# 5_Com_channel.net
KiCad netlist of a schematic drawn in Altium Designer
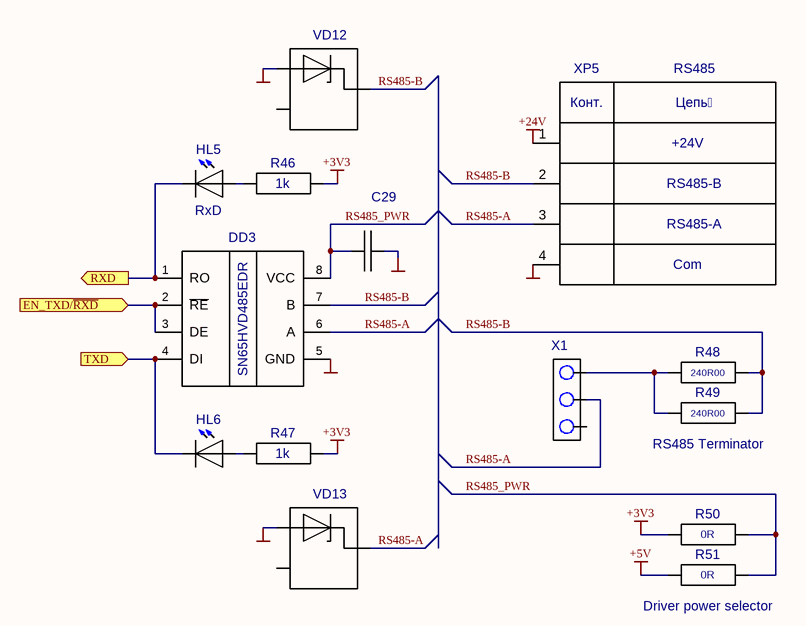
[diagram p0: 5 Com channel.SchDoc]

(export (version "E")
  (design (tool "Eeschema 10.0.6"))
  (components
    (comp (ref "C29")
      (value "C0402")
      (footprint "конденсаторы:0402_CAP")
      (libsource (lib "Com via Eth") (part "C0402"))
    )
    (comp (ref "DD3")
      (value "SN65HVD485EDR")
      (footprint "SO8")
      (description "ADM485AR")
      (libsource (lib "*") (part "ADM485AR"))
    )
    (comp (ref "HL5")
      (value "KP-2012MGC")
      (footprint "индикаторные эл-ты:KP-2012_GRN")
      (libsource (lib "*") (part "KP-2012"))
    )
    (comp (ref "HL6")
      (value "KP-2012SYC")
      (footprint "индикаторные эл-ты:KP-2012_YEL")
      (libsource (lib "*") (part "KP-2012"))
    )
    (comp (ref "R46")
      (value "1k")
      (footprint "резисторы:0603_RES")
      (description "R0603")
      (libsource (lib "*") (part "R0603"))
    )
    (comp (ref "R47")
      (value "1k")
      (footprint "резисторы:0603_RES")
      (description "R0603")
      (libsource (lib "*") (part "R0603"))
    )
    (comp (ref "R48")
      (value "240R00")
      (footprint "резисторы:0805_RES")
      (description "R0805")
      (libsource (lib "Strobe and com via fiber") (part "R0805"))
    )
    (comp (ref "R49")
      (value "240R00")
      (footprint "резисторы:0805_RES")
      (description "R0805")
      (libsource (lib "Strobe and com via fiber") (part "R0805"))
    )
    (comp (ref "R50")
      (value "0R")
      (footprint "резисторы:0402_RES")
      (description "R0402")
      (libsource (lib "резисторы") (part "R0402"))
    )
    (comp (ref "R51")
      (value "0R")
      (footprint "резисторы:0402_RES")
      (description "R0402")
      (libsource (lib "резисторы") (part "R0402"))
    )
    (comp (ref "VD12")
      (value "GSOT12-E3-08")
      (footprint "диоды:SOT-23-(2)")
      (description "Single-line ESD protection device\r\n± 30 kV contact discharge\r\n± 30 kV air discharge")
      (libsource (lib "диоды") (part "GSOT12C"))
    )
    (comp (ref "VD13")
      (value "GSOT12-E3-08")
      (footprint "диоды:SOT-23-(2)")
      (description "Single-line ESD protection device\r\n± 30 kV contact discharge\r\n± 30 kV air discharge")
      (libsource (lib "диоды") (part "GSOT12C"))
    )
    (comp (ref "X1")
      (value "DS1025-01-1*3 P8BV1")
      (footprint "PLS2-3")
      (description "PLS2-3")
      (libsource (lib "*") (part "PLS2-3"))
    )
    (comp (ref "XP5") (value "PH-4") (footprint "PH-4") (libsource (lib "разъёмы") (part "PH-4")))
  )
  (nets
    (net (code "1") (name "+3V3") (class "Default")
      (node (ref "R46") (pin "1") (pinfunction "1_1") (pintype "passive"))
      (node (ref "R47") (pin "1") (pinfunction "1_1") (pintype "passive"))
      (node (ref "R50") (pin "2") (pinfunction "2_2") (pintype "passive"))
    )
    (net (code "2") (name "+5V") (class "Default")
      (node (ref "R51") (pin "2") (pinfunction "2_2") (pintype "passive"))
    )
    (net (code "3") (name "+24V") (class "Default") (node (ref "XP5") (pin "1") (pintype "passive")))
    (net (code "4") (name "/EN_TXD{slash}~{RXD}") (class "Default")
      (node (ref "DD3") (pin "2") (pinfunction "~{RE}_2") (pintype "passive"))
      (node (ref "DD3") (pin "3") (pinfunction "DE_3") (pintype "passive"))
    )
    (net (code "5") (name "/RS485-A") (class "Default")
      (node (ref "DD3") (pin "6") (pinfunction "A_6") (pintype "passive"))
      (node (ref "VD13") (pin "3") (pinfunction "3_3") (pintype "passive"))
      (node (ref "X1") (pin "2") (pinfunction "2_2") (pintype "passive"))
      (node (ref "XP5") (pin "3") (pintype "passive"))
    )
    (net (code "6") (name "/RS485-B") (class "Default")
      (node (ref "DD3") (pin "7") (pinfunction "B_7") (pintype "passive"))
      (node (ref "R48") (pin "1") (pinfunction "1_1") (pintype "passive"))
      (node (ref "R49") (pin "1") (pinfunction "1_1") (pintype "passive"))
      (node (ref "VD12") (pin "3") (pinfunction "3_3") (pintype "passive"))
      (node (ref "XP5") (pin "2") (pintype "passive"))
    )
    (net (code "7") (name "/RS485_PWR") (class "Default")
      (node (ref "C29") (pin "2") (pinfunction "2_2") (pintype "passive"))
      (node (ref "DD3") (pin "8") (pinfunction "VCC_8") (pintype "passive"))
      (node (ref "R50") (pin "1") (pinfunction "1_1") (pintype "passive"))
      (node (ref "R51") (pin "1") (pinfunction "1_1") (pintype "passive"))
    )
    (net (code "8") (name "/RXD") (class "Default")
      (node (ref "DD3") (pin "1") (pinfunction "RO_1") (pintype "passive"))
      (node (ref "HL5") (pin "2") (pinfunction "K_2") (pintype "passive"))
    )
    (net (code "9") (name "/TXD") (class "Default")
      (node (ref "DD3") (pin "4") (pinfunction "DI_4") (pintype "passive"))
      (node (ref "HL6") (pin "2") (pinfunction "K_2") (pintype "passive"))
    )
    (net (code "10") (name "GND") (class "Default")
      (node (ref "C29") (pin "1") (pinfunction "1_1") (pintype "passive"))
      (node (ref "DD3") (pin "5") (pinfunction "GND_5") (pintype "passive"))
      (node (ref "VD12") (pin "1") (pinfunction "1_1") (pintype "passive"))
      (node (ref "VD13") (pin "1") (pinfunction "1_1") (pintype "passive"))
      (node (ref "XP5") (pin "4") (pintype "passive"))
    )
    (net (code "11") (name "Net-(HL5-A)") (class "Default")
      (node (ref "HL5") (pin "1") (pinfunction "A_1") (pintype "passive"))
      (node (ref "R46") (pin "2") (pinfunction "2_2") (pintype "passive"))
    )
    (net (code "12") (name "Net-(HL6-A)") (class "Default")
      (node (ref "HL6") (pin "1") (pinfunction "A_1") (pintype "passive"))
      (node (ref "R47") (pin "2") (pinfunction "2_2") (pintype "passive"))
    )
    (net (code "13") (name "Net-(R48-Pad2)") (class "Default")
      (node (ref "R48") (pin "2") (pinfunction "2_2") (pintype "passive"))
      (node (ref "R49") (pin "2") (pinfunction "2_2") (pintype "passive"))
      (node (ref "X1") (pin "1") (pinfunction "1_1") (pintype "passive"))
    )
    (net (code "14") (name "unconnected-(VD12-Pad2)") (class "Default")
      (node (ref "VD12") (pin "2") (pinfunction "2_2") (pintype "passive"))
    )
    (net (code "15") (name "unconnected-(VD13-Pad2)") (class "Default")
      (node (ref "VD13") (pin "2") (pinfunction "2_2") (pintype "passive"))
    )
    (net (code "16") (name "unconnected-(X1-Pad3)") (class "Default")
      (node (ref "X1") (pin "3") (pinfunction "3_3") (pintype "passive"))
    )
  )
)
